# 5_-_Z7010_POWER_INF.net
KiCad netlist of a schematic drawn in Altium Designer
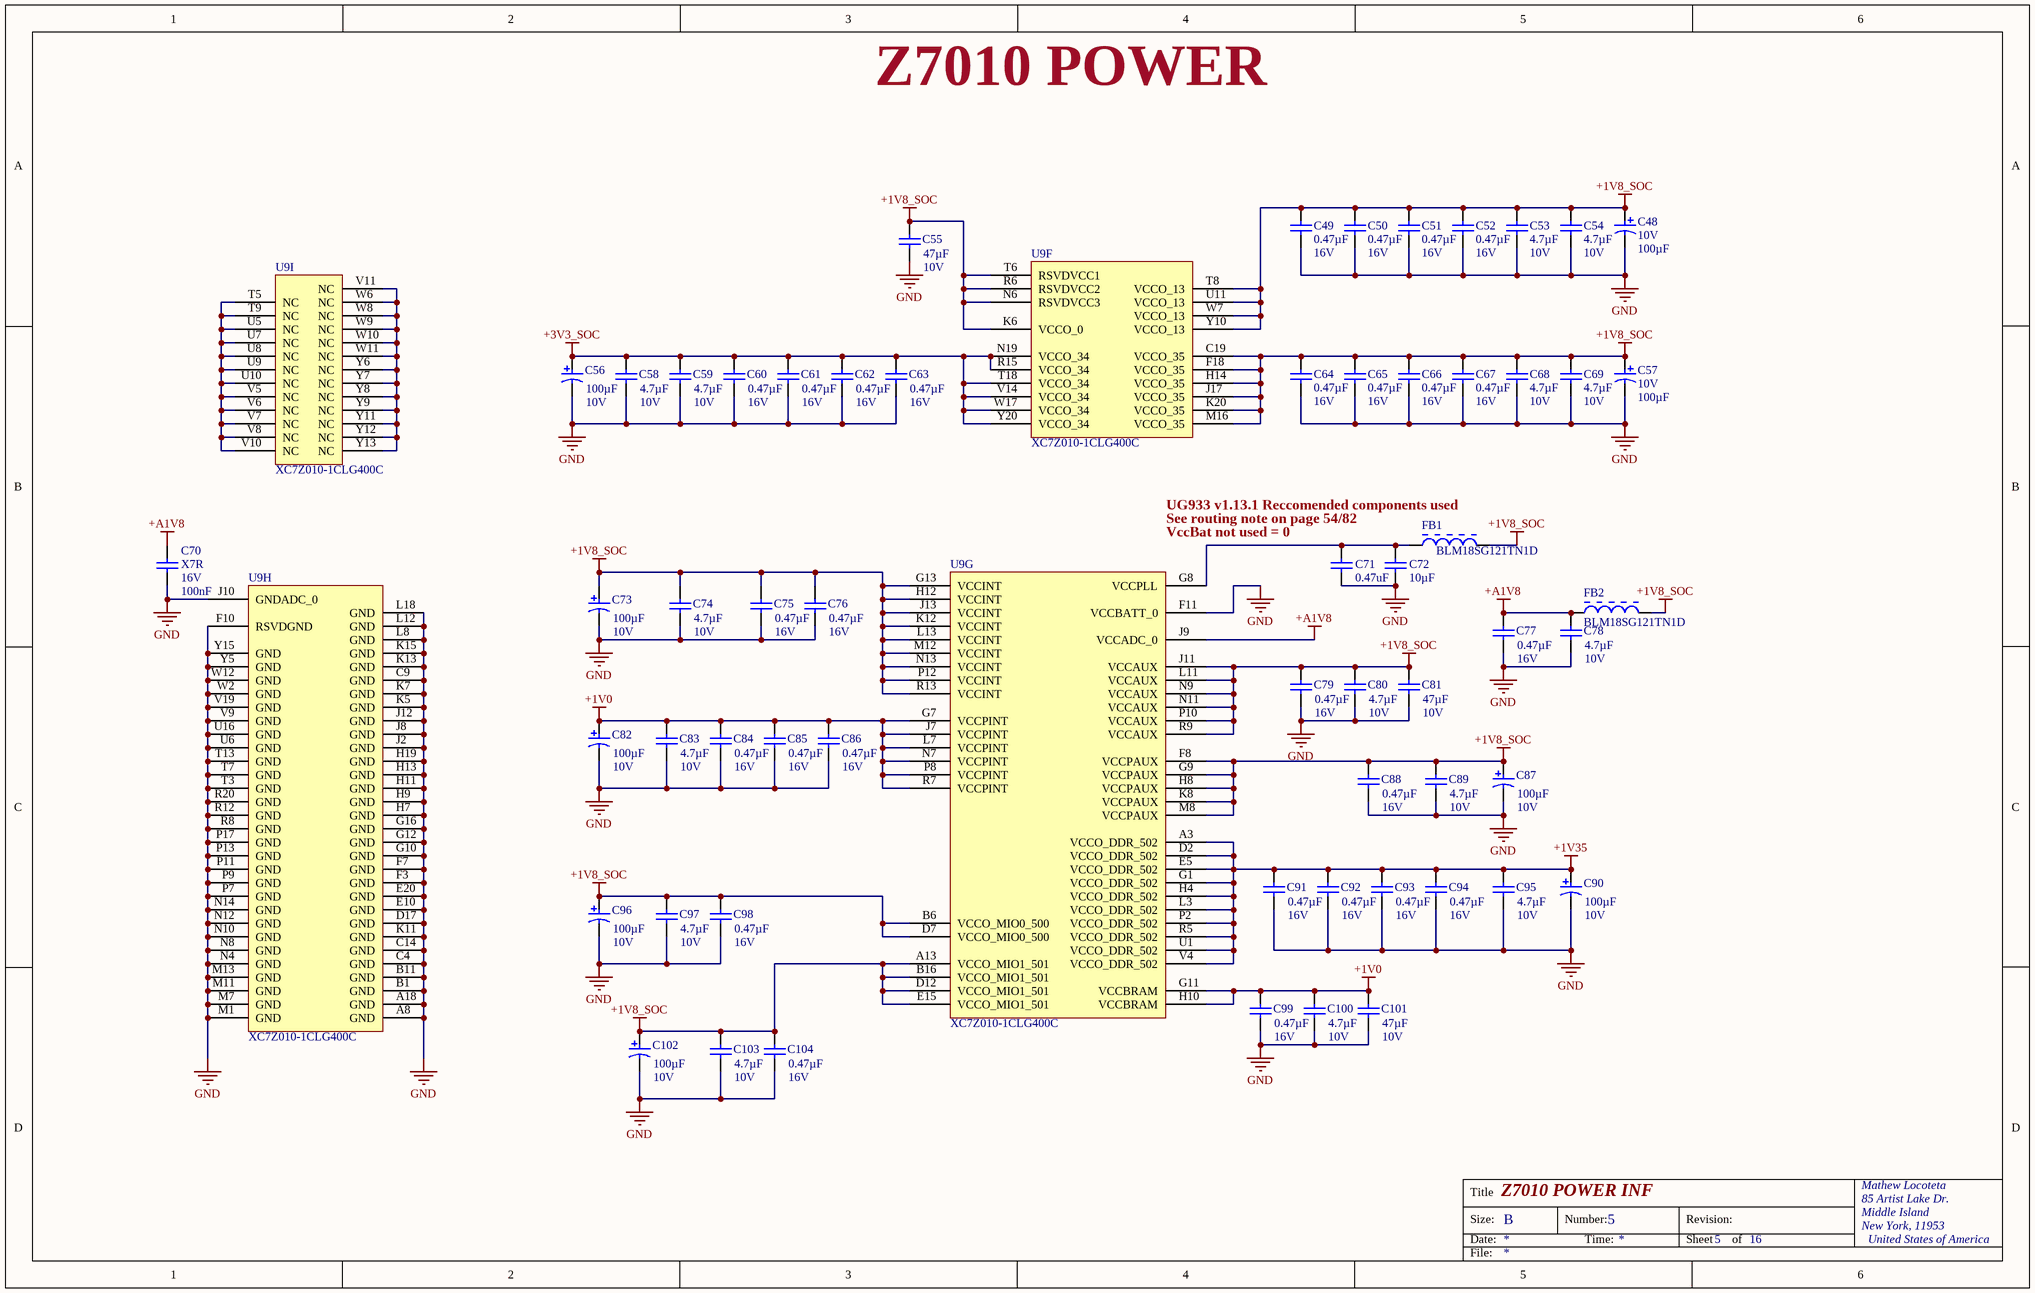
[diagram p0: [5] - Z7010 POWER INF.SchDoc]

(export (version "E")
  (design (tool "Eeschema 10.0.6"))
  (components
    (comp (ref "C48")
      (value "TPSC107K010R0075")
      (footprint "AVX-C2312_L")
      (description "TPS Series, Low ESR, 100 uF, +/- 10%, 10 V, -55 to 125 degC, 2-Pin SMD (2312), RoHS, Tape and Reel")
      (fields
        (field (name "VOLTAGE") "10V")
        (field (name "CAPACITANCE") "100µF")
        (field (name "MANUFACTURER") "AVX")
      )
      (libsource (lib "") (part "CAP-P-2_1"))
    )
    (comp (ref "C49")
      (value "0.47µF")
      (footprint "CAPC1608X90X35NL10T15")
      (fields
        (field (name "MANUFACTURER") "Murata")
        (field (name "PART NUMBER") "GRM188R71C474KA88D")
        (field (name "VOLTAGE") "16V")
      )
      (libsource (lib "Altium Content Vault") (part "CAP"))
    )
    (comp (ref "C50")
      (value "0.47µF")
      (footprint "CAPC1608X90X35NL10T15")
      (fields
        (field (name "MANUFACTURER") "Murata")
        (field (name "PART NUMBER") "GRM188R71C474KA88D")
        (field (name "VOLTAGE") "16V")
      )
      (libsource (lib "Altium Content Vault") (part "CAP"))
    )
    (comp (ref "C51")
      (value "0.47µF")
      (footprint "CAPC1608X90X35NL10T15")
      (fields
        (field (name "MANUFACTURER") "Murata")
        (field (name "PART NUMBER") "GRM188R71C474KA88D")
        (field (name "VOLTAGE") "16V")
      )
      (libsource (lib "Altium Content Vault") (part "CAP"))
    )
    (comp (ref "C52")
      (value "0.47µF")
      (footprint "CAPC1608X90X35NL10T15")
      (fields
        (field (name "MANUFACTURER") "Murata")
        (field (name "PART NUMBER") "GRM188R71C474KA88D")
        (field (name "VOLTAGE") "16V")
      )
      (libsource (lib "Altium Content Vault") (part "CAP"))
    )
    (comp (ref "C53")
      (value "4.7µF")
      (footprint "CAPC2013X152X50ML20T25")
      (fields
        (field (name "PART NUMBER") "0805YC475KAT2A")
        (field (name "MANUFACTURER") "AVX Interconnect / Elco")
        (field (name "VOLTAGE") "10V")
      )
      (libsource (lib "Altium Content Vault") (part "CAP"))
    )
    (comp (ref "C54")
      (value "4.7µF")
      (footprint "CAPC2013X152X50ML20T25")
      (fields
        (field (name "PART NUMBER") "0805YC475KAT2A")
        (field (name "MANUFACTURER") "AVX Interconnect / Elco")
        (field (name "VOLTAGE") "10V")
      )
      (libsource (lib "Altium Content Vault") (part "CAP"))
    )
    (comp (ref "C55")
      (value "GRM32ER71A476ME15L")
      (footprint "MURA-1210_H_2.7_L")
      (description "Chip Capacitor, 47 uF, +/- 20%, 10 V, -55 to 125 degC, 1210 (3225 Metric), RoHS, Tape and Reel")
      (fields
        (field (name "RATED VOLTAGE") "10V")
        (field (name "CAPACITANCE") "47µF")
        (field (name "MANUFACTURER") "Murata")
      )
      (libsource (lib "Altium Content Vault") (part "CAP-NP-2"))
    )
    (comp (ref "C56")
      (value "TPSC107K010R0075")
      (footprint "AVX-C2312_L")
      (description "TPS Series, Low ESR, 100 uF, +/- 10%, 10 V, -55 to 125 degC, 2-Pin SMD (2312), RoHS, Tape and Reel")
      (fields
        (field (name "VOLTAGE") "10V")
        (field (name "CAPACITANCE") "100µF")
        (field (name "MANUFACTURER") "AVX")
      )
      (libsource (lib "Altium Content Vault") (part "CAP-P-2"))
    )
    (comp (ref "C57")
      (value "TPSC107K010R0075")
      (footprint "AVX-C2312_L")
      (description "TPS Series, Low ESR, 100 uF, +/- 10%, 10 V, -55 to 125 degC, 2-Pin SMD (2312), RoHS, Tape and Reel")
      (fields
        (field (name "VOLTAGE") "10V")
        (field (name "CAPACITANCE") "100µF")
        (field (name "MANUFACTURER") "AVX")
      )
      (libsource (lib "") (part "CAP-P-2_1"))
    )
    (comp (ref "C58")
      (value "4.7µF")
      (footprint "CAPC2013X152X50ML20T25")
      (fields
        (field (name "PART NUMBER") "0805YC475KAT2A")
        (field (name "MANUFACTURER") "AVX Interconnect / Elco")
        (field (name "VOLTAGE") "10V")
      )
      (libsource (lib "Altium Content Vault") (part "CAP"))
    )
    (comp (ref "C59")
      (value "4.7µF")
      (footprint "CAPC2013X152X50ML20T25")
      (fields
        (field (name "PART NUMBER") "0805YC475KAT2A")
        (field (name "MANUFACTURER") "AVX Interconnect / Elco")
        (field (name "VOLTAGE") "10V")
      )
      (libsource (lib "Altium Content Vault") (part "CAP"))
    )
    (comp (ref "C60")
      (value "0.47µF")
      (footprint "CAPC1608X90X35NL10T15")
      (fields
        (field (name "MANUFACTURER") "Murata")
        (field (name "PART NUMBER") "GRM188R71C474KA88D")
        (field (name "VOLTAGE") "16V")
      )
      (libsource (lib "Altium Content Vault") (part "CAP"))
    )
    (comp (ref "C61")
      (value "0.47µF")
      (footprint "CAPC1608X90X35NL10T15")
      (fields
        (field (name "MANUFACTURER") "Murata")
        (field (name "PART NUMBER") "GRM188R71C474KA88D")
        (field (name "VOLTAGE") "16V")
      )
      (libsource (lib "Altium Content Vault") (part "CAP"))
    )
    (comp (ref "C62")
      (value "0.47µF")
      (footprint "CAPC1608X90X35NL10T15")
      (fields
        (field (name "MANUFACTURER") "Murata")
        (field (name "PART NUMBER") "GRM188R71C474KA88D")
        (field (name "VOLTAGE") "16V")
      )
      (libsource (lib "Altium Content Vault") (part "CAP"))
    )
    (comp (ref "C63")
      (value "0.47µF")
      (footprint "CAPC1608X90X35NL10T15")
      (fields
        (field (name "MANUFACTURER") "Murata")
        (field (name "PART NUMBER") "GRM188R71C474KA88D")
        (field (name "VOLTAGE") "16V")
      )
      (libsource (lib "Altium Content Vault") (part "CAP"))
    )
    (comp (ref "C64")
      (value "0.47µF")
      (footprint "CAPC1608X90X35NL10T15")
      (fields
        (field (name "MANUFACTURER") "Murata")
        (field (name "PART NUMBER") "GRM188R71C474KA88D")
        (field (name "VOLTAGE") "16V")
      )
      (libsource (lib "Altium Content Vault") (part "CAP"))
    )
    (comp (ref "C65")
      (value "0.47µF")
      (footprint "CAPC1608X90X35NL10T15")
      (fields
        (field (name "MANUFACTURER") "Murata")
        (field (name "PART NUMBER") "GRM188R71C474KA88D")
        (field (name "VOLTAGE") "16V")
      )
      (libsource (lib "Altium Content Vault") (part "CAP"))
    )
    (comp (ref "C66")
      (value "0.47µF")
      (footprint "CAPC1608X90X35NL10T15")
      (fields
        (field (name "MANUFACTURER") "Murata")
        (field (name "PART NUMBER") "GRM188R71C474KA88D")
        (field (name "VOLTAGE") "16V")
      )
      (libsource (lib "Altium Content Vault") (part "CAP"))
    )
    (comp (ref "C67")
      (value "0.47µF")
      (footprint "CAPC1608X90X35NL10T15")
      (fields
        (field (name "MANUFACTURER") "Murata")
        (field (name "PART NUMBER") "GRM188R71C474KA88D")
        (field (name "VOLTAGE") "16V")
      )
      (libsource (lib "Altium Content Vault") (part "CAP"))
    )
    (comp (ref "C68")
      (value "4.7µF")
      (footprint "CAPC2013X152X50ML20T25")
      (fields
        (field (name "PART NUMBER") "0805YC475KAT2A")
        (field (name "MANUFACTURER") "AVX Interconnect / Elco")
        (field (name "VOLTAGE") "10V")
      )
      (libsource (lib "Altium Content Vault") (part "CAP"))
    )
    (comp (ref "C69")
      (value "4.7µF")
      (footprint "CAPC2013X152X50ML20T25")
      (fields
        (field (name "PART NUMBER") "0805YC475KAT2A")
        (field (name "MANUFACTURER") "AVX Interconnect / Elco")
        (field (name "VOLTAGE") "10V")
      )
      (libsource (lib "Altium Content Vault") (part "CAP"))
    )
    (comp (ref "C70")
      (value "100nF 0402 16V")
      (fields
        (field (name "MANUFACTURER") "KEMET")
        (field (name "MANUFACTURER PART NUMBER") "C0402C104J4RACTU")
        (field (name "TOLERANCE") "5%")
        (field (name "DIELECTRIC") "X7R")
        (field (name "VOLTAGE RATING") "16V")
        (field (name "CAPACITANCE") "100nF")
      )
      (libsource (lib "Zynq 7000") (part "C0402C104J4RACTU"))
    )
    (comp (ref "C71")
      (value "0.47uF")
      (footprint "CAPC1005X55X25LL05T10")
      (fields (field (name "MANUFACTURER") "Murata") (field (name "PART NUMBER") "GRM155R60J474KE19D"))
      (libsource (lib "Altium Content Vault") (part "CAP"))
    )
    (comp (ref "C72")
      (value "10µF")
      (footprint "CAPC1608X90X35LL10T15")
      (fields (field (name "PART NUMBER") "GRM188R60G106ME47D") (field (name "MANUFACTURER") "Murata"))
      (libsource (lib "Altium Content Vault") (part "CAP"))
    )
    (comp (ref "C73")
      (value "TPSC107K010R0075")
      (footprint "AVX-C2312_L")
      (description "TPS Series, Low ESR, 100 uF, +/- 10%, 10 V, -55 to 125 degC, 2-Pin SMD (2312), RoHS, Tape and Reel")
      (fields
        (field (name "VOLTAGE") "10V")
        (field (name "CAPACITANCE") "100µF")
        (field (name "MANUFACTURER") "AVX")
      )
      (libsource (lib "Altium Content Vault") (part "CAP-P-2"))
    )
    (comp (ref "C74")
      (value "4.7µF")
      (footprint "CAPC2013X152X50ML20T25")
      (fields
        (field (name "PART NUMBER") "0805YC475KAT2A")
        (field (name "MANUFACTURER") "AVX Interconnect / Elco")
        (field (name "VOLTAGE") "10V")
      )
      (libsource (lib "Altium Content Vault") (part "CAP"))
    )
    (comp (ref "C75")
      (value "0.47µF")
      (footprint "CAPC1608X90X35NL10T15")
      (fields
        (field (name "MANUFACTURER") "Murata")
        (field (name "PART NUMBER") "GRM188R71C474KA88D")
        (field (name "VOLTAGE") "16V")
      )
      (libsource (lib "Altium Content Vault") (part "CAP"))
    )
    (comp (ref "C76")
      (value "0.47µF")
      (footprint "CAPC1608X90X35NL10T15")
      (fields
        (field (name "MANUFACTURER") "Murata")
        (field (name "PART NUMBER") "GRM188R71C474KA88D")
        (field (name "VOLTAGE") "16V")
      )
      (libsource (lib "Altium Content Vault") (part "CAP"))
    )
    (comp (ref "C77")
      (value "0.47µF")
      (footprint "CAPC1608X90X35NL10T15")
      (fields
        (field (name "MANUFACTURER") "Murata")
        (field (name "PART NUMBER") "GRM188R71C474KA88D")
        (field (name "VOLTAGE") "16V")
      )
      (libsource (lib "Altium Content Vault") (part "CAP"))
    )
    (comp (ref "C78")
      (value "4.7µF")
      (footprint "CAPC2013X152X50ML20T25")
      (fields
        (field (name "PART NUMBER") "0805YC475KAT2A")
        (field (name "MANUFACTURER") "AVX Interconnect / Elco")
        (field (name "VOLTAGE") "10V")
      )
      (libsource (lib "Altium Content Vault") (part "CAP"))
    )
    (comp (ref "C79")
      (value "0.47µF")
      (footprint "CAPC1608X90X35NL10T15")
      (fields
        (field (name "MANUFACTURER") "Murata")
        (field (name "PART NUMBER") "GRM188R71C474KA88D")
        (field (name "VOLTAGE") "16V")
      )
      (libsource (lib "Altium Content Vault") (part "CAP"))
    )
    (comp (ref "C80")
      (value "4.7µF")
      (footprint "CAPC2013X152X50ML20T25")
      (fields
        (field (name "PART NUMBER") "0805YC475KAT2A")
        (field (name "MANUFACTURER") "AVX Interconnect / Elco")
        (field (name "VOLTAGE") "10V")
      )
      (libsource (lib "Altium Content Vault") (part "CAP"))
    )
    (comp (ref "C81")
      (value "GRM32ER71A476ME15L")
      (footprint "MURA-1210_H_2.7_L")
      (description "Chip Capacitor, 47 uF, +/- 20%, 10 V, -55 to 125 degC, 1210 (3225 Metric), RoHS, Tape and Reel")
      (fields
        (field (name "RATED VOLTAGE") "10V")
        (field (name "CAPACITANCE") "47µF")
        (field (name "MANUFACTURER") "Murata")
      )
      (libsource (lib "Altium Content Vault") (part "CAP-NP-2"))
    )
    (comp (ref "C82")
      (value "TPSC107K010R0075")
      (footprint "AVX-C2312_L")
      (description "TPS Series, Low ESR, 100 uF, +/- 10%, 10 V, -55 to 125 degC, 2-Pin SMD (2312), RoHS, Tape and Reel")
      (fields
        (field (name "VOLTAGE") "10V")
        (field (name "CAPACITANCE") "100µF")
        (field (name "MANUFACTURER") "AVX")
      )
      (libsource (lib "Altium Content Vault") (part "CAP-P-2"))
    )
    (comp (ref "C83")
      (value "4.7µF")
      (footprint "CAPC2013X152X50ML20T25")
      (fields
        (field (name "PART NUMBER") "0805YC475KAT2A")
        (field (name "MANUFACTURER") "AVX Interconnect / Elco")
        (field (name "VOLTAGE") "10V")
      )
      (libsource (lib "Altium Content Vault") (part "CAP"))
    )
    (comp (ref "C84")
      (value "0.47µF")
      (footprint "CAPC1608X90X35NL10T15")
      (fields
        (field (name "MANUFACTURER") "Murata")
        (field (name "PART NUMBER") "GRM188R71C474KA88D")
        (field (name "VOLTAGE") "16V")
      )
      (libsource (lib "Altium Content Vault") (part "CAP"))
    )
    (comp (ref "C85")
      (value "0.47µF")
      (footprint "CAPC1608X90X35NL10T15")
      (fields
        (field (name "MANUFACTURER") "Murata")
        (field (name "PART NUMBER") "GRM188R71C474KA88D")
        (field (name "VOLTAGE") "16V")
      )
      (libsource (lib "Altium Content Vault") (part "CAP"))
    )
    (comp (ref "C86")
      (value "0.47µF")
      (footprint "CAPC1608X90X35NL10T15")
      (fields
        (field (name "MANUFACTURER") "Murata")
        (field (name "PART NUMBER") "GRM188R71C474KA88D")
        (field (name "VOLTAGE") "16V")
      )
      (libsource (lib "Altium Content Vault") (part "CAP"))
    )
    (comp (ref "C87")
      (value "TPSC107K010R0075")
      (footprint "AVX-C2312_L")
      (description "TPS Series, Low ESR, 100 uF, +/- 10%, 10 V, -55 to 125 degC, 2-Pin SMD (2312), RoHS, Tape and Reel")
      (fields
        (field (name "VOLTAGE") "10V")
        (field (name "CAPACITANCE") "100µF")
        (field (name "MANUFACTURER") "AVX")
      )
      (libsource (lib "Altium Content Vault") (part "CAP-P-2"))
    )
    (comp (ref "C88")
      (value "0.47µF")
      (footprint "CAPC1608X90X35NL10T15")
      (fields
        (field (name "MANUFACTURER") "Murata")
        (field (name "PART NUMBER") "GRM188R71C474KA88D")
        (field (name "VOLTAGE") "16V")
      )
      (libsource (lib "Altium Content Vault") (part "CAP"))
    )
    (comp (ref "C89")
      (value "4.7µF")
      (footprint "CAPC2013X152X50ML20T25")
      (fields
        (field (name "PART NUMBER") "0805YC475KAT2A")
        (field (name "MANUFACTURER") "AVX Interconnect / Elco")
        (field (name "VOLTAGE") "10V")
      )
      (libsource (lib "Altium Content Vault") (part "CAP"))
    )
    (comp (ref "C90")
      (value "TPSC107K010R0075")
      (footprint "AVX-C2312_L")
      (description "TPS Series, Low ESR, 100 uF, +/- 10%, 10 V, -55 to 125 degC, 2-Pin SMD (2312), RoHS, Tape and Reel")
      (fields
        (field (name "VOLTAGE") "10V")
        (field (name "CAPACITANCE") "100µF")
        (field (name "MANUFACTURER") "AVX")
      )
      (libsource (lib "Altium Content Vault") (part "CAP-P-2"))
    )
    (comp (ref "C91")
      (value "0.47µF")
      (footprint "CAPC1608X90X35NL10T15")
      (fields
        (field (name "MANUFACTURER") "Murata")
        (field (name "PART NUMBER") "GRM188R71C474KA88D")
        (field (name "VOLTAGE") "16V")
      )
      (libsource (lib "Altium Content Vault") (part "CAP"))
    )
    (comp (ref "C92")
      (value "0.47µF")
      (footprint "CAPC1608X90X35NL10T15")
      (fields
        (field (name "MANUFACTURER") "Murata")
        (field (name "PART NUMBER") "GRM188R71C474KA88D")
        (field (name "VOLTAGE") "16V")
      )
      (libsource (lib "Altium Content Vault") (part "CAP"))
    )
    (comp (ref "C93")
      (value "0.47µF")
      (footprint "CAPC1608X90X35NL10T15")
      (fields
        (field (name "MANUFACTURER") "Murata")
        (field (name "PART NUMBER") "GRM188R71C474KA88D")
        (field (name "VOLTAGE") "16V")
      )
      (libsource (lib "Altium Content Vault") (part "CAP"))
    )
    (comp (ref "C94")
      (value "0.47µF")
      (footprint "CAPC1608X90X35NL10T15")
      (fields
        (field (name "MANUFACTURER") "Murata")
        (field (name "PART NUMBER") "GRM188R71C474KA88D")
        (field (name "VOLTAGE") "16V")
      )
      (libsource (lib "Altium Content Vault") (part "CAP"))
    )
    (comp (ref "C95")
      (value "4.7µF")
      (footprint "CAPC2013X152X50ML20T25")
      (fields
        (field (name "PART NUMBER") "0805YC475KAT2A")
        (field (name "MANUFACTURER") "AVX Interconnect / Elco")
        (field (name "VOLTAGE") "10V")
      )
      (libsource (lib "Altium Content Vault") (part "CAP"))
    )
    (comp (ref "C96")
      (value "TPSC107K010R0075")
      (footprint "AVX-C2312_L")
      (description "TPS Series, Low ESR, 100 uF, +/- 10%, 10 V, -55 to 125 degC, 2-Pin SMD (2312), RoHS, Tape and Reel")
      (fields
        (field (name "VOLTAGE") "10V")
        (field (name "CAPACITANCE") "100µF")
        (field (name "MANUFACTURER") "AVX")
      )
      (libsource (lib "Altium Content Vault") (part "CAP-P-2"))
    )
    (comp (ref "C97")
      (value "4.7µF")
      (footprint "CAPC2013X152X50ML20T25")
      (fields
        (field (name "PART NUMBER") "0805YC475KAT2A")
        (field (name "MANUFACTURER") "AVX Interconnect / Elco")
        (field (name "VOLTAGE") "10V")
      )
      (libsource (lib "Altium Content Vault") (part "CAP"))
    )
    (comp (ref "C98")
      (value "0.47µF")
      (footprint "CAPC1608X90X35NL10T15")
      (fields
        (field (name "MANUFACTURER") "Murata")
        (field (name "PART NUMBER") "GRM188R71C474KA88D")
        (field (name "VOLTAGE") "16V")
      )
      (libsource (lib "Altium Content Vault") (part "CAP"))
    )
    (comp (ref "C99")
      (value "0.47µF")
      (footprint "CAPC1608X90X35NL10T15")
      (fields
        (field (name "MANUFACTURER") "Murata")
        (field (name "PART NUMBER") "GRM188R71C474KA88D")
        (field (name "VOLTAGE") "16V")
      )
      (libsource (lib "Altium Content Vault") (part "CAP"))
    )
    (comp (ref "C100")
      (value "4.7µF")
      (footprint "CAPC2013X152X50ML20T25")
      (fields
        (field (name "PART NUMBER") "0805YC475KAT2A")
        (field (name "MANUFACTURER") "AVX Interconnect / Elco")
        (field (name "VOLTAGE") "10V")
      )
      (libsource (lib "Altium Content Vault") (part "CAP"))
    )
    (comp (ref "C101")
      (value "GRM32ER71A476ME15L")
      (footprint "MURA-1210_H_2.7_L")
      (description "Chip Capacitor, 47 uF, +/- 20%, 10 V, -55 to 125 degC, 1210 (3225 Metric), RoHS, Tape and Reel")
      (fields
        (field (name "RATED VOLTAGE") "10V")
        (field (name "CAPACITANCE") "47µF")
        (field (name "MANUFACTURER") "Murata")
      )
      (libsource (lib "Altium Content Vault") (part "CAP-NP-2"))
    )
    (comp (ref "C102")
      (value "TPSC107K010R0075")
      (footprint "AVX-C2312_L")
      (description "TPS Series, Low ESR, 100 uF, +/- 10%, 10 V, -55 to 125 degC, 2-Pin SMD (2312), RoHS, Tape and Reel")
      (fields
        (field (name "VOLTAGE") "10V")
        (field (name "CAPACITANCE") "100µF")
        (field (name "MANUFACTURER") "AVX")
      )
      (libsource (lib "Altium Content Vault") (part "CAP-P-2"))
    )
    (comp (ref "C103")
      (value "4.7µF")
      (footprint "CAPC2013X152X50ML20T25")
      (fields
        (field (name "PART NUMBER") "0805YC475KAT2A")
        (field (name "MANUFACTURER") "AVX Interconnect / Elco")
        (field (name "VOLTAGE") "10V")
      )
      (libsource (lib "Altium Content Vault") (part "CAP"))
    )
    (comp (ref "C104")
      (value "0.47µF")
      (footprint "CAPC1608X90X35NL10T15")
      (fields
        (field (name "MANUFACTURER") "Murata")
        (field (name "PART NUMBER") "GRM188R71C474KA88D")
        (field (name "VOLTAGE") "16V")
      )
      (libsource (lib "Altium Content Vault") (part "CAP"))
    )
    (comp (ref "FB1")
      (value "BLM18SG121TN1D")
      (footprint "MURA-BLM18SG-B40-CHIP-2_V3")
      (fields (field (name "MANUFACTURER") "Murata"))
      (libsource (lib "Altium Content Vault") (part "MURA-FB-2"))
    )
    (comp (ref "FB2")
      (value "BLM18SG121TN1D")
      (footprint "MURA-BLM18SG-B40-CHIP-2_V3")
      (fields (field (name "MANUFACTURER") "Murata"))
      (libsource (lib "Altium Content Vault") (part "MURA-FB-2"))
    )
    (comp (ref "U9")
      (value "XC7Z010-1CLG400C")
      (footprint "CLG400")
      (fields (field (name "GENERIC PART NUMBER") "XC7Z010"))
      (libsource (lib "Altium Content Vault") (part "XNLX-XC7Z010-CLG400"))
    )
  )
  (nets
    (net (code "1") (name "+1V0") (class "Default")
      (node (ref "C100") (pin "2") (pinfunction "2_2") (pintype "passive"))
      (node (ref "C101") (pin "2") (pinfunction "2_2") (pintype "passive"))
      (node (ref "C82") (pin "1") (pinfunction "1_1") (pintype "passive"))
      (node (ref "C83") (pin "2") (pinfunction "2_2") (pintype "passive"))
      (node (ref "C84") (pin "2") (pinfunction "2_2") (pintype "passive"))
      (node (ref "C85") (pin "2") (pinfunction "2_2") (pintype "passive"))
      (node (ref "C86") (pin "2") (pinfunction "2_2") (pintype "passive"))
      (node (ref "C99") (pin "2") (pinfunction "2_2") (pintype "passive"))
      (node (ref "U9") (pin "G11") (pinfunction "VCCBRAM_G11") (pintype "power_in"))
      (node (ref "U9") (pin "G7") (pinfunction "VCCPINT_G7") (pintype "power_in"))
      (node (ref "U9") (pin "H10") (pinfunction "VCCBRAM_H10") (pintype "power_in"))
      (node (ref "U9") (pin "J7") (pinfunction "VCCPINT_J7") (pintype "power_in"))
      (node (ref "U9") (pin "L7") (pinfunction "VCCPINT_L7") (pintype "power_in"))
      (node (ref "U9") (pin "N7") (pinfunction "VCCPINT_N7") (pintype "power_in"))
      (node (ref "U9") (pin "P8") (pinfunction "VCCPINT_P8") (pintype "power_in"))
      (node (ref "U9") (pin "R7") (pinfunction "VCCPINT_R7") (pintype "power_in"))
    )
    (net (code "2") (name "+1V8_SOC") (class "Default")
      (node (ref "C102") (pin "1") (pinfunction "1_1") (pintype "passive"))
      (node (ref "C103") (pin "2") (pinfunction "2_2") (pintype "passive"))
      (node (ref "C104") (pin "2") (pinfunction "2_2") (pintype "passive"))
      (node (ref "C48") (pin "1") (pinfunction "1_1") (pintype "passive"))
      (node (ref "C49") (pin "2") (pinfunction "2_2") (pintype "passive"))
      (node (ref "C50") (pin "2") (pinfunction "2_2") (pintype "passive"))
      (node (ref "C51") (pin "2") (pinfunction "2_2") (pintype "passive"))
      (node (ref "C52") (pin "2") (pinfunction "2_2") (pintype "passive"))
      (node (ref "C53") (pin "2") (pinfunction "2_2") (pintype "passive"))
      (node (ref "C54") (pin "2") (pinfunction "2_2") (pintype "passive"))
      (node (ref "C55") (pin "2") (pinfunction "2_2") (pintype "passive"))
      (node (ref "C57") (pin "1") (pinfunction "1_1") (pintype "passive"))
      (node (ref "C64") (pin "2") (pinfunction "2_2") (pintype "passive"))
      (node (ref "C65") (pin "2") (pinfunction "2_2") (pintype "passive"))
      (node (ref "C66") (pin "2") (pinfunction "2_2") (pintype "passive"))
      (node (ref "C67") (pin "2") (pinfunction "2_2") (pintype "passive"))
      (node (ref "C68") (pin "2") (pinfunction "2_2") (pintype "passive"))
      (node (ref "C69") (pin "2") (pinfunction "2_2") (pintype "passive"))
      (node (ref "C73") (pin "1") (pinfunction "1_1") (pintype "passive"))
      (node (ref "C74") (pin "2") (pinfunction "2_2") (pintype "passive"))
      (node (ref "C75") (pin "2") (pinfunction "2_2") (pintype "passive"))
      (node (ref "C76") (pin "2") (pinfunction "2_2") (pintype "passive"))
      (node (ref "C79") (pin "2") (pinfunction "2_2") (pintype "passive"))
      (node (ref "C80") (pin "2") (pinfunction "2_2") (pintype "passive"))
      (node (ref "C81") (pin "2") (pinfunction "2_2") (pintype "passive"))
      (node (ref "C87") (pin "1") (pinfunction "1_1") (pintype "passive"))
      (node (ref "C88") (pin "2") (pinfunction "2_2") (pintype "passive"))
      (node (ref "C89") (pin "2") (pinfunction "2_2") (pintype "passive"))
      (node (ref "C96") (pin "1") (pinfunction "1_1") (pintype "passive"))
      (node (ref "C97") (pin "2") (pinfunction "2_2") (pintype "passive"))
      (node (ref "C98") (pin "2") (pinfunction "2_2") (pintype "passive"))
      (node (ref "FB1") (pin "2") (pinfunction "2_2") (pintype "passive"))
      (node (ref "FB2") (pin "2") (pinfunction "2_2") (pintype "passive"))
      (node (ref "U9") (pin "A13") (pinfunction "VCCO_MIO1_501_A13") (pintype "power_in"))
      (node (ref "U9") (pin "B16") (pinfunction "VCCO_MIO1_501_B16") (pintype "power_in"))
      (node (ref "U9") (pin "B6") (pinfunction "VCCO_MIO0_500_B6") (pintype "power_in"))
      (node (ref "U9") (pin "C19") (pinfunction "VCCO_35_C19") (pintype "power_in"))
      (node (ref "U9") (pin "D12") (pinfunction "VCCO_MIO1_501_D12") (pintype "power_in"))
      (node (ref "U9") (pin "D7") (pinfunction "VCCO_MIO0_500_D7") (pintype "power_in"))
      (node (ref "U9") (pin "E15") (pinfunction "VCCO_MIO1_501_E15") (pintype "power_in"))
      (node (ref "U9") (pin "F18") (pinfunction "VCCO_35_F18") (pintype "power_in"))
      (node (ref "U9") (pin "F8") (pinfunction "VCCPAUX_F8") (pintype "power_in"))
      (node (ref "U9") (pin "G13") (pinfunction "VCCINT_G13") (pintype "power_in"))
      (node (ref "U9") (pin "G9") (pinfunction "VCCPAUX_G9") (pintype "power_in"))
      (node (ref "U9") (pin "H12") (pinfunction "VCCINT_H12") (pintype "power_in"))
      (node (ref "U9") (pin "H14") (pinfunction "VCCO_35_H14") (pintype "power_in"))
      (node (ref "U9") (pin "H8") (pinfunction "VCCPAUX_H8") (pintype "power_in"))
      (node (ref "U9") (pin "J11") (pinfunction "VCCAUX_J11") (pintype "power_in"))
      (node (ref "U9") (pin "J13") (pinfunction "VCCINT_J13") (pintype "power_in"))
      (node (ref "U9") (pin "J17") (pinfunction "VCCO_35_J17") (pintype "power_in"))
      (node (ref "U9") (pin "K12") (pinfunction "VCCINT_K12") (pintype "power_in"))
      (node (ref "U9") (pin "K20") (pinfunction "VCCO_35_K20") (pintype "power_in"))
      (node (ref "U9") (pin "K6") (pinfunction "VCCO_0_K6") (pintype "power_in"))
      (node (ref "U9") (pin "K8") (pinfunction "VCCPAUX_K8") (pintype "power_in"))
      (node (ref "U9") (pin "L11") (pinfunction "VCCAUX_L11") (pintype "power_in"))
      (node (ref "U9") (pin "L13") (pinfunction "VCCINT_L13") (pintype "power_in"))
      (node (ref "U9") (pin "M12") (pinfunction "VCCINT_M12") (pintype "power_in"))
      (node (ref "U9") (pin "M16") (pinfunction "VCCO_35_M16") (pintype "power_in"))
      (node (ref "U9") (pin "M8") (pinfunction "VCCPAUX_M8") (pintype "power_in"))
      (node (ref "U9") (pin "N11") (pinfunction "VCCAUX_N11") (pintype "power_in"))
      (node (ref "U9") (pin "N13") (pinfunction "VCCINT_N13") (pintype "power_in"))
      (node (ref "U9") (pin "N6") (pinfunction "RSVDVCC3_N6") (pintype "power_in"))
      (node (ref "U9") (pin "N9") (pinfunction "VCCAUX_N9") (pintype "power_in"))
      (node (ref "U9") (pin "P10") (pinfunction "VCCAUX_P10") (pintype "power_in"))
      (node (ref "U9") (pin "P12") (pinfunction "VCCINT_P12") (pintype "power_in"))
      (node (ref "U9") (pin "R13") (pinfunction "VCCINT_R13") (pintype "power_in"))
      (node (ref "U9") (pin "R6") (pinfunction "RSVDVCC2_R6") (pintype "power_in"))
      (node (ref "U9") (pin "R9") (pinfunction "VCCAUX_R9") (pintype "power_in"))
      (node (ref "U9") (pin "T6") (pinfunction "RSVDVCC1_T6") (pintype "power_in"))
      (node (ref "U9") (pin "T8") (pinfunction "VCCO_13_T8") (pintype "power_in"))
      (node (ref "U9") (pin "U11") (pinfunction "VCCO_13_U11") (pintype "power_in"))
      (node (ref "U9") (pin "W7") (pinfunction "VCCO_13_W7") (pintype "power_in"))
      (node (ref "U9") (pin "Y10") (pinfunction "VCCO_13_Y10") (pintype "power_in"))
    )
    (net (code "3") (name "+1V35") (class "Default")
      (node (ref "C90") (pin "1") (pinfunction "1_1") (pintype "passive"))
      (node (ref "C91") (pin "2") (pinfunction "2_2") (pintype "passive"))
      (node (ref "C92") (pin "2") (pinfunction "2_2") (pintype "passive"))
      (node (ref "C93") (pin "2") (pinfunction "2_2") (pintype "passive"))
      (node (ref "C94") (pin "2") (pinfunction "2_2") (pintype "passive"))
      (node (ref "C95") (pin "2") (pinfunction "2_2") (pintype "passive"))
      (node (ref "U9") (pin "A3") (pinfunction "VCCO_DDR_502_A3") (pintype "power_in"))
      (node (ref "U9") (pin "D2") (pinfunction "VCCO_DDR_502_D2") (pintype "power_in"))
      (node (ref "U9") (pin "E5") (pinfunction "VCCO_DDR_502_E5") (pintype "power_in"))
      (node (ref "U9") (pin "G1") (pinfunction "VCCO_DDR_502_G1") (pintype "power_in"))
      (node (ref "U9") (pin "H4") (pinfunction "VCCO_DDR_502_H4") (pintype "power_in"))
      (node (ref "U9") (pin "L3") (pinfunction "VCCO_DDR_502_L3") (pintype "power_in"))
      (node (ref "U9") (pin "P2") (pinfunction "VCCO_DDR_502_P2") (pintype "power_in"))
      (node (ref "U9") (pin "R5") (pinfunction "VCCO_DDR_502_R5") (pintype "power_in"))
      (node (ref "U9") (pin "U1") (pinfunction "VCCO_DDR_502_U1") (pintype "power_in"))
      (node (ref "U9") (pin "V4") (pinfunction "VCCO_DDR_502_V4") (pintype "power_in"))
    )
    (net (code "4") (name "+3V3_SOC") (class "Default")
      (node (ref "C56") (pin "1") (pinfunction "1_1") (pintype "passive"))
      (node (ref "C58") (pin "2") (pinfunction "2_2") (pintype "passive"))
      (node (ref "C59") (pin "2") (pinfunction "2_2") (pintype "passive"))
      (node (ref "C60") (pin "2") (pinfunction "2_2") (pintype "passive"))
      (node (ref "C61") (pin "2") (pinfunction "2_2") (pintype "passive"))
      (node (ref "C62") (pin "2") (pinfunction "2_2") (pintype "passive"))
      (node (ref "C63") (pin "2") (pinfunction "2_2") (pintype "passive"))
      (node (ref "U9") (pin "N19") (pinfunction "VCCO_34_N19") (pintype "power_in"))
      (node (ref "U9") (pin "R15") (pinfunction "VCCO_34_R15") (pintype "power_in"))
      (node (ref "U9") (pin "T18") (pinfunction "VCCO_34_T18") (pintype "power_in"))
      (node (ref "U9") (pin "V14") (pinfunction "VCCO_34_V14") (pintype "power_in"))
      (node (ref "U9") (pin "W17") (pinfunction "VCCO_34_W17") (pintype "power_in"))
      (node (ref "U9") (pin "Y20") (pinfunction "VCCO_34_Y20") (pintype "power_in"))
    )
    (net (code "5") (name "+A1V8") (class "Default")
      (node (ref "C70") (pin "2") (pinfunction "2_2") (pintype "passive"))
      (node (ref "C77") (pin "2") (pinfunction "2_2") (pintype "passive"))
      (node (ref "C78") (pin "2") (pinfunction "2_2") (pintype "passive"))
      (node (ref "FB2") (pin "1") (pinfunction "1_1") (pintype "passive"))
      (node (ref "U9") (pin "J9") (pinfunction "VCCADC_0_J9") (pintype "power_in"))
    )
    (net (code "6") (name "GND") (class "Default")
      (node (ref "C100") (pin "1") (pinfunction "1_1") (pintype "passive"))
      (node (ref "C101") (pin "1") (pinfunction "1_1") (pintype "passive"))
      (node (ref "C102") (pin "2") (pinfunction "2_2") (pintype "passive"))
      (node (ref "C103") (pin "1") (pinfunction "1_1") (pintype "passive"))
      (node (ref "C104") (pin "1") (pinfunction "1_1") (pintype "passive"))
      (node (ref "C48") (pin "2") (pinfunction "2_2") (pintype "passive"))
      (node (ref "C49") (pin "1") (pinfunction "1_1") (pintype "passive"))
      (node (ref "C50") (pin "1") (pinfunction "1_1") (pintype "passive"))
      (node (ref "C51") (pin "1") (pinfunction "1_1") (pintype "passive"))
      (node (ref "C52") (pin "1") (pinfunction "1_1") (pintype "passive"))
      (node (ref "C53") (pin "1") (pinfunction "1_1") (pintype "passive"))
      (node (ref "C54") (pin "1") (pinfunction "1_1") (pintype "passive"))
      (node (ref "C55") (pin "1") (pinfunction "1_1") (pintype "passive"))
      (node (ref "C56") (pin "2") (pinfunction "2_2") (pintype "passive"))
      (node (ref "C57") (pin "2") (pinfunction "2_2") (pintype "passive"))
      (node (ref "C58") (pin "1") (pinfunction "1_1") (pintype "passive"))
      (node (ref "C59") (pin "1") (pinfunction "1_1") (pintype "passive"))
      (node (ref "C60") (pin "1") (pinfunction "1_1") (pintype "passive"))
      (node (ref "C61") (pin "1") (pinfunction "1_1") (pintype "passive"))
      (node (ref "C62") (pin "1") (pinfunction "1_1") (pintype "passive"))
      (node (ref "C63") (pin "1") (pinfunction "1_1") (pintype "passive"))
      (node (ref "C64") (pin "1") (pinfunction "1_1") (pintype "passive"))
      (node (ref "C65") (pin "1") (pinfunction "1_1") (pintype "passive"))
      (node (ref "C66") (pin "1") (pinfunction "1_1") (pintype "passive"))
      (node (ref "C67") (pin "1") (pinfunction "1_1") (pintype "passive"))
      (node (ref "C68") (pin "1") (pinfunction "1_1") (pintype "passive"))
      (node (ref "C69") (pin "1") (pinfunction "1_1") (pintype "passive"))
      (node (ref "C70") (pin "1") (pinfunction "1_1") (pintype "passive"))
      (node (ref "C71") (pin "1") (pinfunction "1_1") (pintype "passive"))
      (node (ref "C72") (pin "1") (pinfunction "1_1") (pintype "passive"))
      (node (ref "C73") (pin "2") (pinfunction "2_2") (pintype "passive"))
      (node (ref "C74") (pin "1") (pinfunction "1_1") (pintype "passive"))
      (node (ref "C75") (pin "1") (pinfunction "1_1") (pintype "passive"))
      (node (ref "C76") (pin "1") (pinfunction "1_1") (pintype "passive"))
      (node (ref "C77") (pin "1") (pinfunction "1_1") (pintype "passive"))
      (node (ref "C78") (pin "1") (pinfunction "1_1") (pintype "passive"))
      (node (ref "C79") (pin "1") (pinfunction "1_1") (pintype "passive"))
      (node (ref "C80") (pin "1") (pinfunction "1_1") (pintype "passive"))
      (node (ref "C81") (pin "1") (pinfunction "1_1") (pintype "passive"))
      (node (ref "C82") (pin "2") (pinfunction "2_2") (pintype "passive"))
      (node (ref "C83") (pin "1") (pinfunction "1_1") (pintype "passive"))
      (node (ref "C84") (pin "1") (pinfunction "1_1") (pintype "passive"))
      (node (ref "C85") (pin "1") (pinfunction "1_1") (pintype "passive"))
      (node (ref "C86") (pin "1") (pinfunction "1_1") (pintype "passive"))
      (node (ref "C87") (pin "2") (pinfunction "2_2") (pintype "passive"))
      (node (ref "C88") (pin "1") (pinfunction "1_1") (pintype "passive"))
      (node (ref "C89") (pin "1") (pinfunction "1_1") (pintype "passive"))
      (node (ref "C90") (pin "2") (pinfunction "2_2") (pintype "passive"))
      (node (ref "C91") (pin "1") (pinfunction "1_1") (pintype "passive"))
      (node (ref "C92") (pin "1") (pinfunction "1_1") (pintype "passive"))
      (node (ref "C93") (pin "1") (pinfunction "1_1") (pintype "passive"))
      (node (ref "C94") (pin "1") (pinfunction "1_1") (pintype "passive"))
      (node (ref "C95") (pin "1") (pinfunction "1_1") (pintype "passive"))
      (node (ref "C96") (pin "2") (pinfunction "2_2") (pintype "passive"))
      (node (ref "C97") (pin "1") (pinfunction "1_1") (pintype "passive"))
      (node (ref "C98") (pin "1") (pinfunction "1_1") (pintype "passive"))
      (node (ref "C99") (pin "1") (pinfunction "1_1") (pintype "passive"))
      (node (ref "U9") (pin "A18") (pinfunction "GND_A18") (pintype "power_in"))
      (node (ref "U9") (pin "A8") (pinfunction "GND_A8") (pintype "power_in"))
      (node (ref "U9") (pin "B1") (pinfunction "GND_B1") (pintype "power_in"))
      (node (ref "U9") (pin "B11") (pinfunction "GND_B11") (pintype "power_in"))
      (node (ref "U9") (pin "C14") (pinfunction "GND_C14") (pintype "power_in"))
      (node (ref "U9") (pin "C4") (pinfunction "GND_C4") (pintype "power_in"))
      (node (ref "U9") (pin "C9") (pinfunction "GND_C9") (pintype "power_in"))
      (node (ref "U9") (pin "D17") (pinfunction "GND_D17") (pintype "power_in"))
      (node (ref "U9") (pin "E10") (pinfunction "GND_E10") (pintype "power_in"))
      (node (ref "U9") (pin "E20") (pinfunction "GND_E20") (pintype "power_in"))
      (node (ref "U9") (pin "F10") (pinfunction "RSVDGND_F10") (pintype "power_in"))
      (node (ref "U9") (pin "F11") (pinfunction "VCCBATT_0_F11") (pintype "power_in"))
      (node (ref "U9") (pin "F3") (pinfunction "GND_F3") (pintype "power_in"))
      (node (ref "U9") (pin "F7") (pinfunction "GND_F7") (pintype "power_in"))
      (node (ref "U9") (pin "G10") (pinfunction "GND_G10") (pintype "power_in"))
      (node (ref "U9") (pin "G12") (pinfunction "GND_G12") (pintype "power_in"))
      (node (ref "U9") (pin "G16") (pinfunction "GND_G16") (pintype "power_in"))
      (node (ref "U9") (pin "H11") (pinfunction "GND_H11") (pintype "power_in"))
      (node (ref "U9") (pin "H13") (pinfunction "GND_H13") (pintype "power_in"))
      (node (ref "U9") (pin "H19") (pinfunction "GND_H19") (pintype "power_in"))
      (node (ref "U9") (pin "H7") (pinfunction "GND_H7") (pintype "power_in"))
      (node (ref "U9") (pin "H9") (pinfunction "GND_H9") (pintype "power_in"))
      (node (ref "U9") (pin "J10") (pinfunction "GNDADC_0_J10") (pintype "power_in"))
      (node (ref "U9") (pin "J12") (pinfunction "GND_J12") (pintype "power_in"))
      (node (ref "U9") (pin "J2") (pinfunction "GND_J2") (pintype "power_in"))
      (node (ref "U9") (pin "J8") (pinfunction "GND_J8") (pintype "power_in"))
      (node (ref "U9") (pin "K11") (pinfunction "GND_K11") (pintype "power_in"))
      (node (ref "U9") (pin "K13") (pinfunction "GND_K13") (pintype "power_in"))
      (node (ref "U9") (pin "K15") (pinfunction "GND_K15") (pintype "power_in"))
      (node (ref "U9") (pin "K5") (pinfunction "GND_K5") (pintype "power_in"))
      (node (ref "U9") (pin "K7") (pinfunction "GND_K7") (pintype "power_in"))
      (node (ref "U9") (pin "L12") (pinfunction "GND_L12") (pintype "power_in"))
      (node (ref "U9") (pin "L18") (pinfunction "GND_L18") (pintype "power_in"))
      (node (ref "U9") (pin "L8") (pinfunction "GND_L8") (pintype "power_in"))
      (node (ref "U9") (pin "M1") (pinfunction "GND_M1") (pintype "power_in"))
      (node (ref "U9") (pin "M11") (pinfunction "GND_M11") (pintype "power_in"))
      (node (ref "U9") (pin "M13") (pinfunction "GND_M13") (pintype "power_in"))
      (node (ref "U9") (pin "M7") (pinfunction "GND_M7") (pintype "power_in"))
      (node (ref "U9") (pin "N10") (pinfunction "GND_N10") (pintype "power_in"))
      (node (ref "U9") (pin "N12") (pinfunction "GND_N12") (pintype "power_in"))
      (node (ref "U9") (pin "N14") (pinfunction "GND_N14") (pintype "power_in"))
      (node (ref "U9") (pin "N4") (pinfunction "GND_N4") (pintype "power_in"))
      (node (ref "U9") (pin "N8") (pinfunction "GND_N8") (pintype "power_in"))
      (node (ref "U9") (pin "P11") (pinfunction "GND_P11") (pintype "power_in"))
      (node (ref "U9") (pin "P13") (pinfunction "GND_P13") (pintype "power_in"))
      (node (ref "U9") (pin "P17") (pinfunction "GND_P17") (pintype "power_in"))
      (node (ref "U9") (pin "P7") (pinfunction "GND_P7") (pintype "power_in"))
      (node (ref "U9") (pin "P9") (pinfunction "GND_P9") (pintype "power_in"))
      (node (ref "U9") (pin "R12") (pinfunction "GND_R12") (pintype "power_in"))
      (node (ref "U9") (pin "R20") (pinfunction "GND_R20") (pintype "power_in"))
      (node (ref "U9") (pin "R8") (pinfunction "GND_R8") (pintype "power_in"))
      (node (ref "U9") (pin "T13") (pinfunction "GND_T13") (pintype "power_in"))
      (node (ref "U9") (pin "T3") (pinfunction "GND_T3") (pintype "power_in"))
      (node (ref "U9") (pin "T7") (pinfunction "GND_T7") (pintype "power_in"))
      (node (ref "U9") (pin "U16") (pinfunction "GND_U16") (pintype "power_in"))
      (node (ref "U9") (pin "U6") (pinfunction "GND_U6") (pintype "power_in"))
      (node (ref "U9") (pin "V19") (pinfunction "GND_V19") (pintype "power_in"))
      (node (ref "U9") (pin "V9") (pinfunction "GND_V9") (pintype "power_in"))
      (node (ref "U9") (pin "W12") (pinfunction "GND_W12") (pintype "power_in"))
      (node (ref "U9") (pin "W2") (pinfunction "GND_W2") (pintype "power_in"))
      (node (ref "U9") (pin "Y15") (pinfunction "GND_Y15") (pintype "power_in"))
      (node (ref "U9") (pin "Y5") (pinfunction "GND_Y5") (pintype "power_in"))
    )
    (net (code "7") (name "Net-(U9G-VCCPLL)") (class "Default")
      (node (ref "C71") (pin "2") (pinfunction "2_2") (pintype "passive"))
      (node (ref "C72") (pin "2") (pinfunction "2_2") (pintype "passive"))
      (node (ref "FB1") (pin "1") (pinfunction "1_1") (pintype "passive"))
      (node (ref "U9") (pin "G8") (pinfunction "VCCPLL_G8") (pintype "power_in"))
    )
    (net (code "8") (name "Net-(U9I-NC-PadT5)") (class "Default")
      (node (ref "U9") (pin "T5") (pinfunction "NC_T5") (pintype "passive"))
      (node (ref "U9") (pin "T9") (pinfunction "NC_T9") (pintype "passive"))
      (node (ref "U9") (pin "U10") (pinfunction "NC_U10") (pintype "passive"))
      (node (ref "U9") (pin "U5") (pinfunction "NC_U5") (pintype "passive"))
      (node (ref "U9") (pin "U7") (pinfunction "NC_U7") (pintype "passive"))
      (node (ref "U9") (pin "U8") (pinfunction "NC_U8") (pintype "passive"))
      (node (ref "U9") (pin "U9") (pinfunction "NC_U9") (pintype "passive"))
      (node (ref "U9") (pin "V10") (pinfunction "NC_V10") (pintype "passive"))
      (node (ref "U9") (pin "V5") (pinfunction "NC_V5") (pintype "passive"))
      (node (ref "U9") (pin "V6") (pinfunction "NC_V6") (pintype "passive"))
      (node (ref "U9") (pin "V7") (pinfunction "NC_V7") (pintype "passive"))
      (node (ref "U9") (pin "V8") (pinfunction "NC_V8") (pintype "passive"))
    )
    (net (code "9") (name "Net-(U9I-NC-PadV11)") (class "Default")
      (node (ref "U9") (pin "V11") (pinfunction "NC_V11") (pintype "passive"))
      (node (ref "U9") (pin "W10") (pinfunction "NC_W10") (pintype "passive"))
      (node (ref "U9") (pin "W11") (pinfunction "NC_W11") (pintype "passive"))
      (node (ref "U9") (pin "W6") (pinfunction "NC_W6") (pintype "passive"))
      (node (ref "U9") (pin "W8") (pinfunction "NC_W8") (pintype "passive"))
      (node (ref "U9") (pin "W9") (pinfunction "NC_W9") (pintype "passive"))
      (node (ref "U9") (pin "Y11") (pinfunction "NC_Y11") (pintype "passive"))
      (node (ref "U9") (pin "Y12") (pinfunction "NC_Y12") (pintype "passive"))
      (node (ref "U9") (pin "Y13") (pinfunction "NC_Y13") (pintype "passive"))
      (node (ref "U9") (pin "Y6") (pinfunction "NC_Y6") (pintype "passive"))
      (node (ref "U9") (pin "Y7") (pinfunction "NC_Y7") (pintype "passive"))
      (node (ref "U9") (pin "Y8") (pinfunction "NC_Y8") (pintype "passive"))
      (node (ref "U9") (pin "Y9") (pinfunction "NC_Y9") (pintype "passive"))
    )
  )
)
